# LED_Logic.net
KiCad netlist of a schematic drawn in Altium Designer
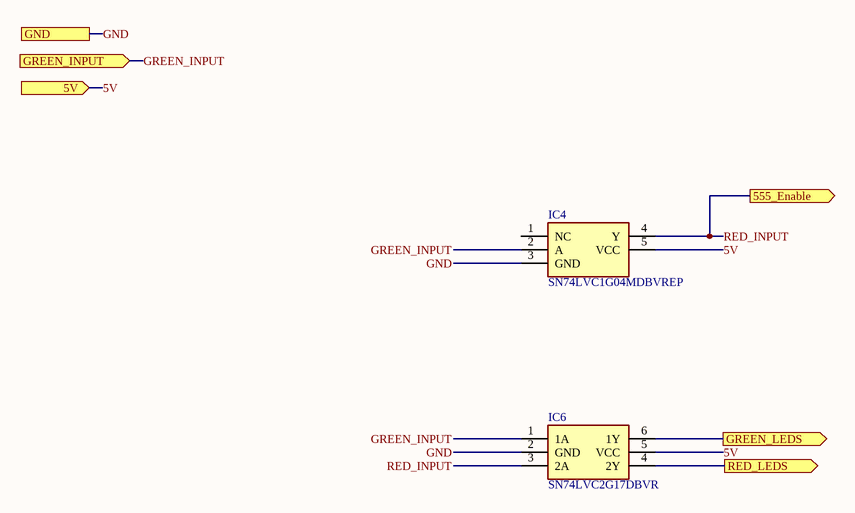
[diagram p0: LED_Logic.SchDoc]

(export (version "E")
  (design (tool "Eeschema 10.0.6"))
  (components
    (comp (ref "IC4")
      (value "SN74LVC1G04MDBVREP")
      (footprint "SOT95P280X145-5N")
      (description "Integrated Circuit")
      (fields (field (name "MOUSER PART NUMBER") "595-SN74LVC04MDBVREP"))
      (libsource (lib "SamacSys") (part "SN74LVC1G04MDBVREP"))
    )
    (comp (ref "IC6")
      (value "SN74LVC2G17DBVR")
      (footprint "SamacSys:SOT95P280X145-6N")
      (description "Integrated Circuit")
      (fields (field (name "MOUSER PART NUMBER") "595-SN74LVC2G17DBVR"))
      (libsource (lib "SamacSys") (part "SN74LVC2G17DBVR"))
    )
  )
  (nets
    (net (code "1") (name "/5V") (class "Default")
      (node (ref "IC4") (pin "5") (pinfunction "VCC_5") (pintype "passive"))
      (node (ref "IC6") (pin "5") (pinfunction "VCC_5") (pintype "passive"))
    )
    (net (code "2") (name "/GND") (class "Default")
      (node (ref "IC4") (pin "3") (pinfunction "GND_3") (pintype "passive"))
      (node (ref "IC6") (pin "2") (pinfunction "GND_2") (pintype "passive"))
    )
    (net (code "3") (name "/GREEN_INPUT") (class "Default")
      (node (ref "IC4") (pin "2") (pinfunction "A_2") (pintype "passive"))
      (node (ref "IC6") (pin "1") (pinfunction "1A_1") (pintype "passive"))
    )
    (net (code "4") (name "/GREEN_LEDS") (class "Default")
      (node (ref "IC6") (pin "6") (pinfunction "1Y_6") (pintype "passive"))
    )
    (net (code "5") (name "/RED_INPUT") (class "Default")
      (node (ref "IC4") (pin "4") (pinfunction "Y_4") (pintype "passive"))
      (node (ref "IC6") (pin "3") (pinfunction "2A_3") (pintype "passive"))
    )
    (net (code "6") (name "/RED_LEDS") (class "Default")
      (node (ref "IC6") (pin "4") (pinfunction "2Y_4") (pintype "passive"))
    )
    (net (code "7") (name "unconnected-(IC4-NC-Pad1)") (class "Default")
      (node (ref "IC4") (pin "1") (pinfunction "NC_1") (pintype "passive"))
    )
  )
)
